# full.net
KiCad netlist of a schematic drawn in EAGLE
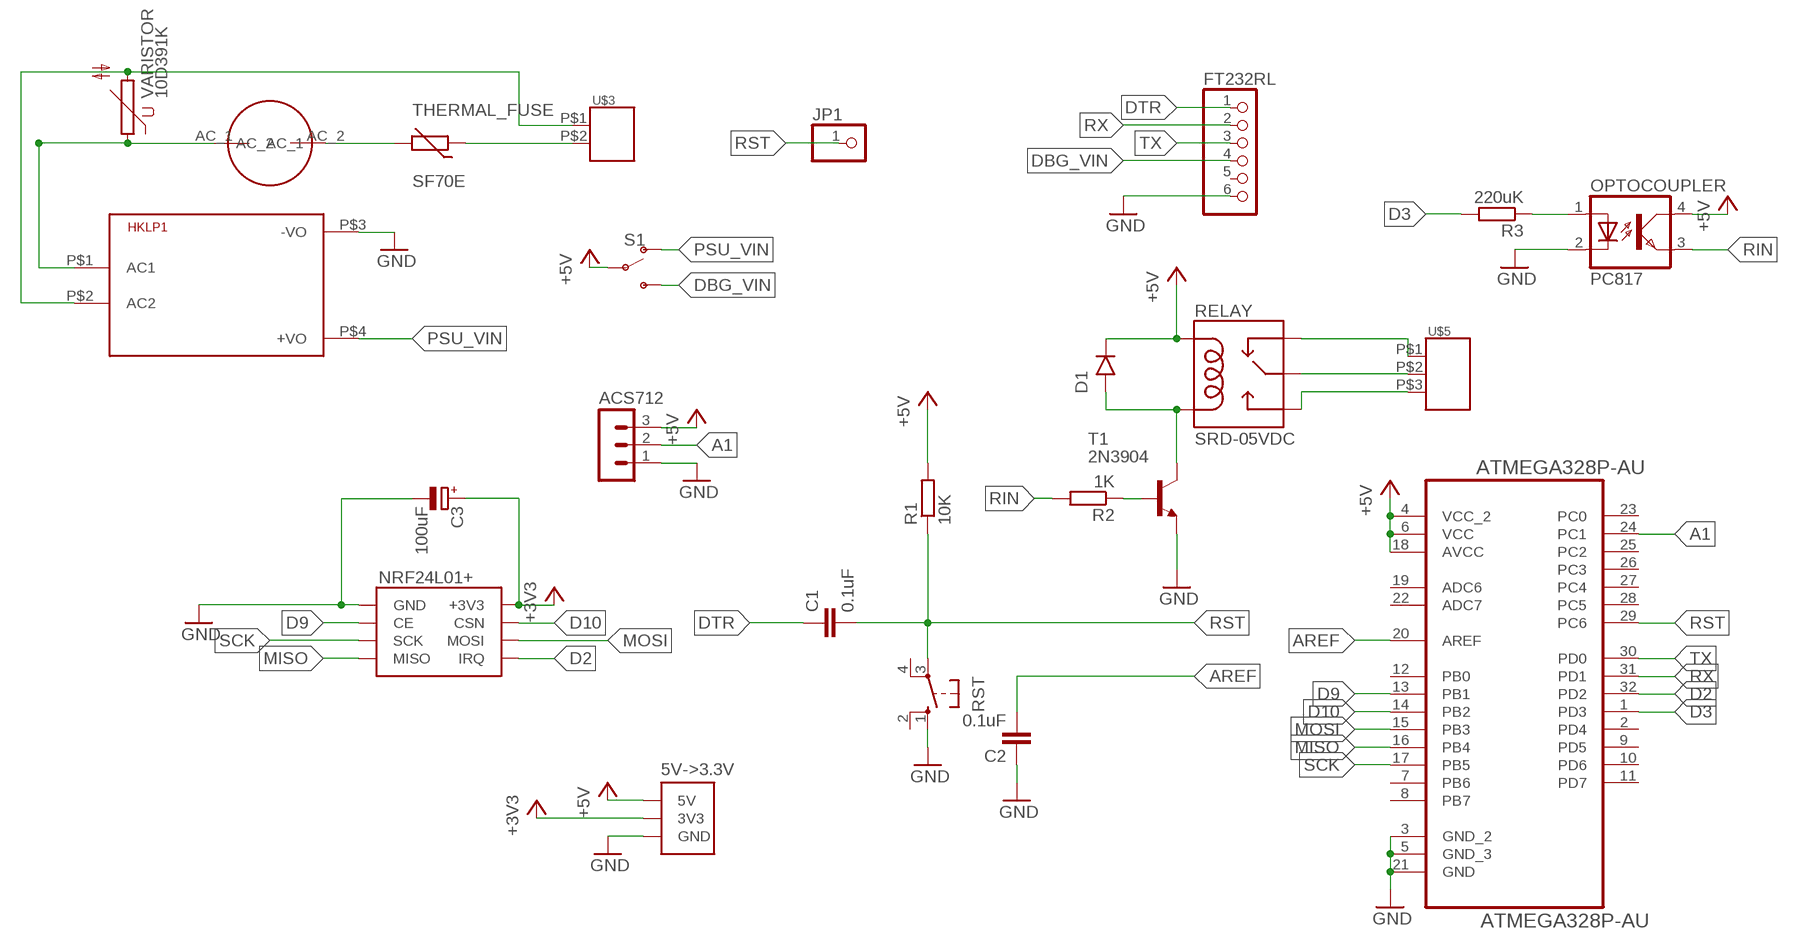
[diagram p0: schematic, sheet 1]

(export (version "E")
  (design (tool "Eeschema 10.0.6"))
  (components
    (comp (ref "5V->3.3V")
      (value "AMS1117_VERT")
      (footprint "eagle-import:AMS1117_VERT")
      (libsource (lib "eagle-import") (part "AMS1117_VERT"))
    )
    (comp (ref "ACS712")
      (value "MA03-1")
      (footprint "eagle-import:MA03-1")
      (libsource (lib "eagle-import") (part "MA03-1"))
    )
    (comp (ref "ATMEGA328P-AU")
      (value "ATMEGA328P-AU")
      (footprint "eagle-import:QFP80P900X900X120-32N")
      (libsource (lib "eagle-import") (part "ATMEGA328P-AU"))
    )
    (comp (ref "C1")
      (value "0.1uF")
      (footprint "eagle-import:C050-030X075")
      (libsource (lib "eagle-import") (part "C-EU050-030X075"))
    )
    (comp (ref "C2")
      (value "0.1uF")
      (footprint "eagle-import:C050-030X075")
      (libsource (lib "eagle-import") (part "C-EU050-030X075"))
    )
    (comp (ref "C3")
      (value "100uF")
      (footprint "eagle-import:E2,5-6")
      (libsource (lib "eagle-import") (part "CPOL-EUE2.5-6"))
    )
    (comp (ref "D1")
      (value "1N4001")
      (footprint "eagle-import:DO41-10")
      (libsource (lib "eagle-import") (part "1N4001"))
    )
    (comp (ref "FT232RL")
      (value "PINHD-1X6")
      (footprint "eagle-import:1X06")
      (libsource (lib "eagle-import") (part "PINHD-1X6"))
    )
    (comp (ref "FUSE")
      (value "R3-24")
      (footprint "eagle-import:R3-24")
      (libsource (lib "eagle-import") (part "R3-24"))
    )
    (comp (ref "HKLP1")
      (value "HKLPM01")
      (footprint "eagle-import:HKLPM01")
      (libsource (lib "eagle-import") (part "HKLPM01"))
    )
    (comp (ref "JP1")
      (value "PINHD-1X1")
      (footprint "eagle-import:1X01")
      (libsource (lib "eagle-import") (part "PINHD-1X1"))
    )
    (comp (ref "NRF24L01+")
      (value "RADIO_NRF24L1")
      (footprint "eagle-import:NRF24L1")
      (libsource (lib "eagle-import") (part "RADIO_NRF24L1"))
    )
    (comp (ref "OPTOCOUPLER")
      (value "PC817")
      (footprint "eagle-import:DIL04")
      (fields (field (name "MPN") "PC817X4J000F"))
      (libsource (lib "eagle-import") (part "PC817"))
    )
    (comp (ref "R1")
      (value "10K")
      (footprint "eagle-import:0204_5")
      (libsource (lib "eagle-import") (part "R-EU_0204/5"))
    )
    (comp (ref "R2")
      (value "1K")
      (footprint "eagle-import:0204_5")
      (libsource (lib "eagle-import") (part "R-EU_0204/5"))
    )
    (comp (ref "R3")
      (value "220uK")
      (footprint "eagle-import:0204_5")
      (libsource (lib "eagle-import") (part "R-EU_0204/5"))
    )
    (comp (ref "RELAY")
      (value "SRD-05VDC")
      (footprint "eagle-import:SRD-05VDC-SL-C")
      (libsource (lib "eagle-import") (part "RELAYPTH"))
    )
    (comp (ref "RST")
      (value "10-XX")
      (footprint "eagle-import:B3F-10XX")
      (fields (field (name "MPN") "B3F-1000"))
      (libsource (lib "eagle-import") (part "10-XX"))
    )
    (comp (ref "S1")
      (value "SWITCH-SPDT-PTH-11.6X4.0MM")
      (footprint "eagle-import:SWITCH_SPDT_PTH_11.6X4.0MM")
      (libsource (lib "eagle-import") (part "SWITCH-SPDT-PTH-11.6X4.0MM"))
    )
    (comp (ref "T1")
      (value "2N3904")
      (footprint "eagle-import:TO92")
      (libsource (lib "eagle-import") (part "2N3904"))
    )
    (comp (ref "THERMAL_FUSE")
      (value "SF70E")
      (footprint "eagle-import:R-7,5")
      (libsource (lib "eagle-import") (part "THERMISTOR_R-7,5"))
    )
    (comp (ref "U$3")
      (value "CONNECTOR_2SCREW")
      (footprint "eagle-import:SCREW_2")
      (libsource (lib "eagle-import") (part "CONNECTOR_2SCREW"))
    )
    (comp (ref "U$5")
      (value "CONNECTOR_3SCREW")
      (footprint "eagle-import:SCREW_3")
      (libsource (lib "eagle-import") (part "CONNECTOR_3SCREW"))
    )
    (comp (ref "VARISTOR")
      (value "10D391K")
      (footprint "eagle-import:S10K385")
      (libsource (lib "eagle-import") (part "S10K385"))
    )
  )
  (nets
    (net (code "1") (name "+3V3") (class "Default")
      (node (ref "5V->3.3V") (pin "3V3") (pinfunction "3V3_3V3") (pintype "power_in"))
      (node (ref "C3") (pin "+") (pinfunction "+_+") (pintype "passive"))
      (node (ref "NRF24L01+") (pin "+3V3") (pinfunction "+3V3_+3V3") (pintype "power_in"))
    )
    (net (code "2") (name "+5V") (class "Default")
      (node (ref "5V->3.3V") (pin "5V") (pinfunction "5V_5V") (pintype "power_in"))
      (node (ref "ACS712") (pin "3") (pinfunction "3_3") (pintype "passive"))
      (node (ref "ATMEGA328P-AU") (pin "18") (pinfunction "AVCC_18") (pintype "power_in"))
      (node (ref "ATMEGA328P-AU") (pin "4") (pinfunction "VCC_2_4") (pintype "power_in"))
      (node (ref "ATMEGA328P-AU") (pin "6") (pinfunction "VCC_6") (pintype "power_in"))
      (node (ref "D1") (pin "C") (pinfunction "CATHODE_C") (pintype "passive"))
      (node (ref "OPTOCOUPLER") (pin "4") (pinfunction "COL_4") (pintype "passive"))
      (node (ref "R1") (pin "2") (pinfunction "2_2") (pintype "passive"))
      (node (ref "RELAY") (pin "COIL1") (pinfunction "COIL1_COIL1") (pintype "bidirectional"))
      (node (ref "S1") (pin "2") (pinfunction "P_2") (pintype "passive"))
    )
    (net (code "3") (name "A1") (class "Default")
      (node (ref "ACS712") (pin "2") (pinfunction "2_2") (pintype "passive"))
      (node (ref "ATMEGA328P-AU") (pin "24") (pinfunction "PC1_24") (pintype "bidirectional"))
    )
    (net (code "4") (name "AREF") (class "Default")
      (node (ref "ATMEGA328P-AU") (pin "20") (pinfunction "AREF_20") (pintype "input"))
      (node (ref "C2") (pin "2") (pinfunction "2_2") (pintype "passive"))
    )
    (net (code "5") (name "D2") (class "Default")
      (node (ref "ATMEGA328P-AU") (pin "32") (pinfunction "PD2_32") (pintype "bidirectional"))
      (node (ref "NRF24L01+") (pin "IRQ") (pinfunction "IRQ_IRQ") (pintype "bidirectional"))
    )
    (net (code "6") (name "D3") (class "Default")
      (node (ref "ATMEGA328P-AU") (pin "1") (pinfunction "PD3_1") (pintype "bidirectional"))
      (node (ref "R3") (pin "2") (pinfunction "2_2") (pintype "passive"))
    )
    (net (code "7") (name "D9") (class "Default")
      (node (ref "ATMEGA328P-AU") (pin "13") (pinfunction "PB1_13") (pintype "bidirectional"))
      (node (ref "NRF24L01+") (pin "CE") (pinfunction "CE_CE") (pintype "bidirectional"))
    )
    (net (code "8") (name "D10") (class "Default")
      (node (ref "ATMEGA328P-AU") (pin "14") (pinfunction "PB2_14") (pintype "bidirectional"))
      (node (ref "NRF24L01+") (pin "CSN") (pinfunction "CSN_CSN") (pintype "bidirectional"))
    )
    (net (code "9") (name "DBG_VIN") (class "Default")
      (node (ref "FT232RL") (pin "4") (pinfunction "4_4") (pintype "passive"))
      (node (ref "S1") (pin "3") (pinfunction "S_3") (pintype "passive"))
    )
    (net (code "10") (name "DTR") (class "Default")
      (node (ref "C1") (pin "1") (pinfunction "1_1") (pintype "passive"))
      (node (ref "FT232RL") (pin "1") (pinfunction "1_1") (pintype "passive"))
    )
    (net (code "11") (name "GND") (class "Default")
      (node (ref "5V->3.3V") (pin "GND") (pinfunction "GND_GND") (pintype "power_in"))
      (node (ref "ACS712") (pin "1") (pinfunction "1_1") (pintype "passive"))
      (node (ref "ATMEGA328P-AU") (pin "21") (pinfunction "GND_21") (pintype "passive"))
      (node (ref "ATMEGA328P-AU") (pin "3") (pinfunction "GND_2_3") (pintype "passive"))
      (node (ref "ATMEGA328P-AU") (pin "5") (pinfunction "GND_3_5") (pintype "passive"))
      (node (ref "C2") (pin "1") (pinfunction "1_1") (pintype "passive"))
      (node (ref "C3") (pin "-") (pinfunction "-_-") (pintype "passive"))
      (node (ref "FT232RL") (pin "6") (pinfunction "6_6") (pintype "passive"))
      (node (ref "HKLP1") (pin "P$3") (pinfunction "-VO_P$3") (pintype "bidirectional"))
      (node (ref "NRF24L01+") (pin "GND") (pinfunction "GND_GND") (pintype "power_in"))
      (node (ref "OPTOCOUPLER") (pin "2") (pinfunction "C_2") (pintype "passive"))
      (node (ref "RST") (pin "1") (pinfunction "S_1") (pintype "passive"))
      (node (ref "T1") (pin "3") (pinfunction "E_3") (pintype "passive"))
    )
    (net (code "12") (name "MISO") (class "Default")
      (node (ref "ATMEGA328P-AU") (pin "16") (pinfunction "PB4_16") (pintype "bidirectional"))
      (node (ref "NRF24L01+") (pin "MISO") (pinfunction "MISO_MISO") (pintype "bidirectional"))
    )
    (net (code "13") (name "MOSI") (class "Default")
      (node (ref "ATMEGA328P-AU") (pin "15") (pinfunction "PB3_15") (pintype "bidirectional"))
      (node (ref "NRF24L01+") (pin "MOSI") (pinfunction "MOSI_MOSI") (pintype "bidirectional"))
    )
    (net (code "14") (name "Net-(D1-ANODE)") (class "Default")
      (node (ref "D1") (pin "A") (pinfunction "ANODE_A") (pintype "passive"))
      (node (ref "RELAY") (pin "COIL0") (pinfunction "COIL0_COIL0") (pintype "bidirectional"))
      (node (ref "T1") (pin "1") (pinfunction "C_1") (pintype "passive"))
    )
    (net (code "15") (name "Net-(FUSE-PadAC_2)") (class "Default")
      (node (ref "FUSE") (pin "AC_2") (pinfunction "AC_2_AC_2") (pintype "bidirectional"))
      (node (ref "THERMAL_FUSE") (pin "2") (pinfunction "2_2") (pintype "passive"))
    )
    (net (code "16") (name "Net-(HKLP1-AC1)") (class "Default")
      (node (ref "FUSE") (pin "AC_1") (pinfunction "AC_1_AC_1") (pintype "bidirectional"))
      (node (ref "HKLP1") (pin "P$1") (pinfunction "AC1_P$1") (pintype "bidirectional"))
      (node (ref "VARISTOR") (pin "1") (pinfunction "1_1") (pintype "passive"))
    )
    (net (code "17") (name "Net-(HKLP1-AC2)") (class "Default")
      (node (ref "HKLP1") (pin "P$2") (pinfunction "AC2_P$2") (pintype "bidirectional"))
      (node (ref "U$3") (pin "P$1") (pinfunction "1_P$1") (pintype "bidirectional"))
      (node (ref "VARISTOR") (pin "2") (pinfunction "2_2") (pintype "passive"))
    )
    (net (code "18") (name "Net-(OPTOCOUPLER-A)") (class "Default")
      (node (ref "OPTOCOUPLER") (pin "1") (pinfunction "A_1") (pintype "passive"))
      (node (ref "R3") (pin "1") (pinfunction "1_1") (pintype "passive"))
    )
    (net (code "19") (name "Net-(RELAY-SWCLOSE)") (class "Default")
      (node (ref "RELAY") (pin "SWCLOSED") (pinfunction "SWCLOSE_SWCLOSED") (pintype "bidirectional"))
      (node (ref "U$5") (pin "P$1") (pinfunction "1_P$1") (pintype "bidirectional"))
    )
    (net (code "20") (name "Net-(T1-B)") (class "Default")
      (node (ref "R2") (pin "1") (pinfunction "1_1") (pintype "passive"))
      (node (ref "T1") (pin "2") (pinfunction "B_2") (pintype "passive"))
    )
    (net (code "21") (name "Net-(U$3-2)") (class "Default")
      (node (ref "THERMAL_FUSE") (pin "1") (pinfunction "1_1") (pintype "passive"))
      (node (ref "U$3") (pin "P$2") (pinfunction "2_P$2") (pintype "bidirectional"))
    )
    (net (code "22") (name "Net-(U$5-2)") (class "Default")
      (node (ref "RELAY") (pin "SWCOMMON") (pinfunction "SWCOMMON_SWCOMMON") (pintype "bidirectional"))
      (node (ref "U$5") (pin "P$2") (pinfunction "2_P$2") (pintype "bidirectional"))
    )
    (net (code "23") (name "Net-(U$5-3)") (class "Default")
      (node (ref "RELAY") (pin "SWOPEN") (pinfunction "SWOPEN_SWOPEN") (pintype "bidirectional"))
      (node (ref "U$5") (pin "P$3") (pinfunction "3_P$3") (pintype "bidirectional"))
    )
    (net (code "24") (name "PSU_VIN") (class "Default")
      (node (ref "HKLP1") (pin "P$4") (pinfunction "+VO_P$4") (pintype "bidirectional"))
      (node (ref "S1") (pin "1") (pinfunction "O_1") (pintype "passive"))
    )
    (net (code "25") (name "RIN") (class "Default")
      (node (ref "OPTOCOUPLER") (pin "3") (pinfunction "EMIT_3") (pintype "passive"))
      (node (ref "R2") (pin "2") (pinfunction "2_2") (pintype "passive"))
    )
    (net (code "26") (name "RST") (class "Default")
      (node (ref "ATMEGA328P-AU") (pin "29") (pinfunction "PC6_29") (pintype "bidirectional"))
      (node (ref "C1") (pin "2") (pinfunction "2_2") (pintype "passive"))
      (node (ref "JP1") (pin "1") (pinfunction "1_1") (pintype "passive"))
      (node (ref "R1") (pin "1") (pinfunction "1_1") (pintype "passive"))
      (node (ref "RST") (pin "3") (pinfunction "P_3") (pintype "passive"))
    )
    (net (code "27") (name "RX") (class "Default")
      (node (ref "ATMEGA328P-AU") (pin "31") (pinfunction "PD1_31") (pintype "bidirectional"))
      (node (ref "FT232RL") (pin "2") (pinfunction "2_2") (pintype "passive"))
    )
    (net (code "28") (name "SCK") (class "Default")
      (node (ref "ATMEGA328P-AU") (pin "17") (pinfunction "PB5_17") (pintype "bidirectional"))
      (node (ref "NRF24L01+") (pin "SCK") (pinfunction "SCK_SCK") (pintype "bidirectional"))
    )
    (net (code "29") (name "TX") (class "Default")
      (node (ref "ATMEGA328P-AU") (pin "30") (pinfunction "PD0_30") (pintype "bidirectional"))
      (node (ref "FT232RL") (pin "3") (pinfunction "3_3") (pintype "passive"))
    )
    (net (code "30") (name "unconnected-(ATMEGA328P-AU-ADC6-Pad19)") (class "Default")
      (node (ref "ATMEGA328P-AU") (pin "19") (pinfunction "ADC6_19") (pintype "input"))
    )
    (net (code "31") (name "unconnected-(ATMEGA328P-AU-ADC7-Pad22)") (class "Default")
      (node (ref "ATMEGA328P-AU") (pin "22") (pinfunction "ADC7_22") (pintype "input"))
    )
    (net (code "32") (name "unconnected-(ATMEGA328P-AU-PB0-Pad12)") (class "Default")
      (node (ref "ATMEGA328P-AU") (pin "12") (pinfunction "PB0_12") (pintype "bidirectional"))
    )
    (net (code "33") (name "unconnected-(ATMEGA328P-AU-PB6-Pad7)") (class "Default")
      (node (ref "ATMEGA328P-AU") (pin "7") (pinfunction "PB6_7") (pintype "bidirectional"))
    )
    (net (code "34") (name "unconnected-(ATMEGA328P-AU-PB7-Pad8)") (class "Default")
      (node (ref "ATMEGA328P-AU") (pin "8") (pinfunction "PB7_8") (pintype "bidirectional"))
    )
    (net (code "35") (name "unconnected-(ATMEGA328P-AU-PC0-Pad23)") (class "Default")
      (node (ref "ATMEGA328P-AU") (pin "23") (pinfunction "PC0_23") (pintype "bidirectional"))
    )
    (net (code "36") (name "unconnected-(ATMEGA328P-AU-PC2-Pad25)") (class "Default")
      (node (ref "ATMEGA328P-AU") (pin "25") (pinfunction "PC2_25") (pintype "bidirectional"))
    )
    (net (code "37") (name "unconnected-(ATMEGA328P-AU-PC3-Pad26)") (class "Default")
      (node (ref "ATMEGA328P-AU") (pin "26") (pinfunction "PC3_26") (pintype "bidirectional"))
    )
    (net (code "38") (name "unconnected-(ATMEGA328P-AU-PC4-Pad27)") (class "Default")
      (node (ref "ATMEGA328P-AU") (pin "27") (pinfunction "PC4_27") (pintype "bidirectional"))
    )
    (net (code "39") (name "unconnected-(ATMEGA328P-AU-PC5-Pad28)") (class "Default")
      (node (ref "ATMEGA328P-AU") (pin "28") (pinfunction "PC5_28") (pintype "bidirectional"))
    )
    (net (code "40") (name "unconnected-(ATMEGA328P-AU-PD4-Pad2)") (class "Default")
      (node (ref "ATMEGA328P-AU") (pin "2") (pinfunction "PD4_2") (pintype "bidirectional"))
    )
    (net (code "41") (name "unconnected-(ATMEGA328P-AU-PD5-Pad9)") (class "Default")
      (node (ref "ATMEGA328P-AU") (pin "9") (pinfunction "PD5_9") (pintype "bidirectional"))
    )
    (net (code "42") (name "unconnected-(ATMEGA328P-AU-PD6-Pad10)") (class "Default")
      (node (ref "ATMEGA328P-AU") (pin "10") (pinfunction "PD6_10") (pintype "bidirectional"))
    )
    (net (code "43") (name "unconnected-(ATMEGA328P-AU-PD7-Pad11)") (class "Default")
      (node (ref "ATMEGA328P-AU") (pin "11") (pinfunction "PD7_11") (pintype "bidirectional"))
    )
    (net (code "44") (name "unconnected-(FT232RL-Pad5)") (class "Default")
      (node (ref "FT232RL") (pin "5") (pinfunction "5_5") (pintype "passive"))
    )
    (net (code "45") (name "unconnected-(RST-P1-Pad4)") (class "Default")
      (node (ref "RST") (pin "4") (pinfunction "P1_4") (pintype "passive"))
    )
    (net (code "46") (name "unconnected-(RST-S1-Pad2)") (class "Default")
      (node (ref "RST") (pin "2") (pinfunction "S1_2") (pintype "passive"))
    )
  )
)
